# sch.net
KiCad netlist of a schematic drawn in Altium Designer
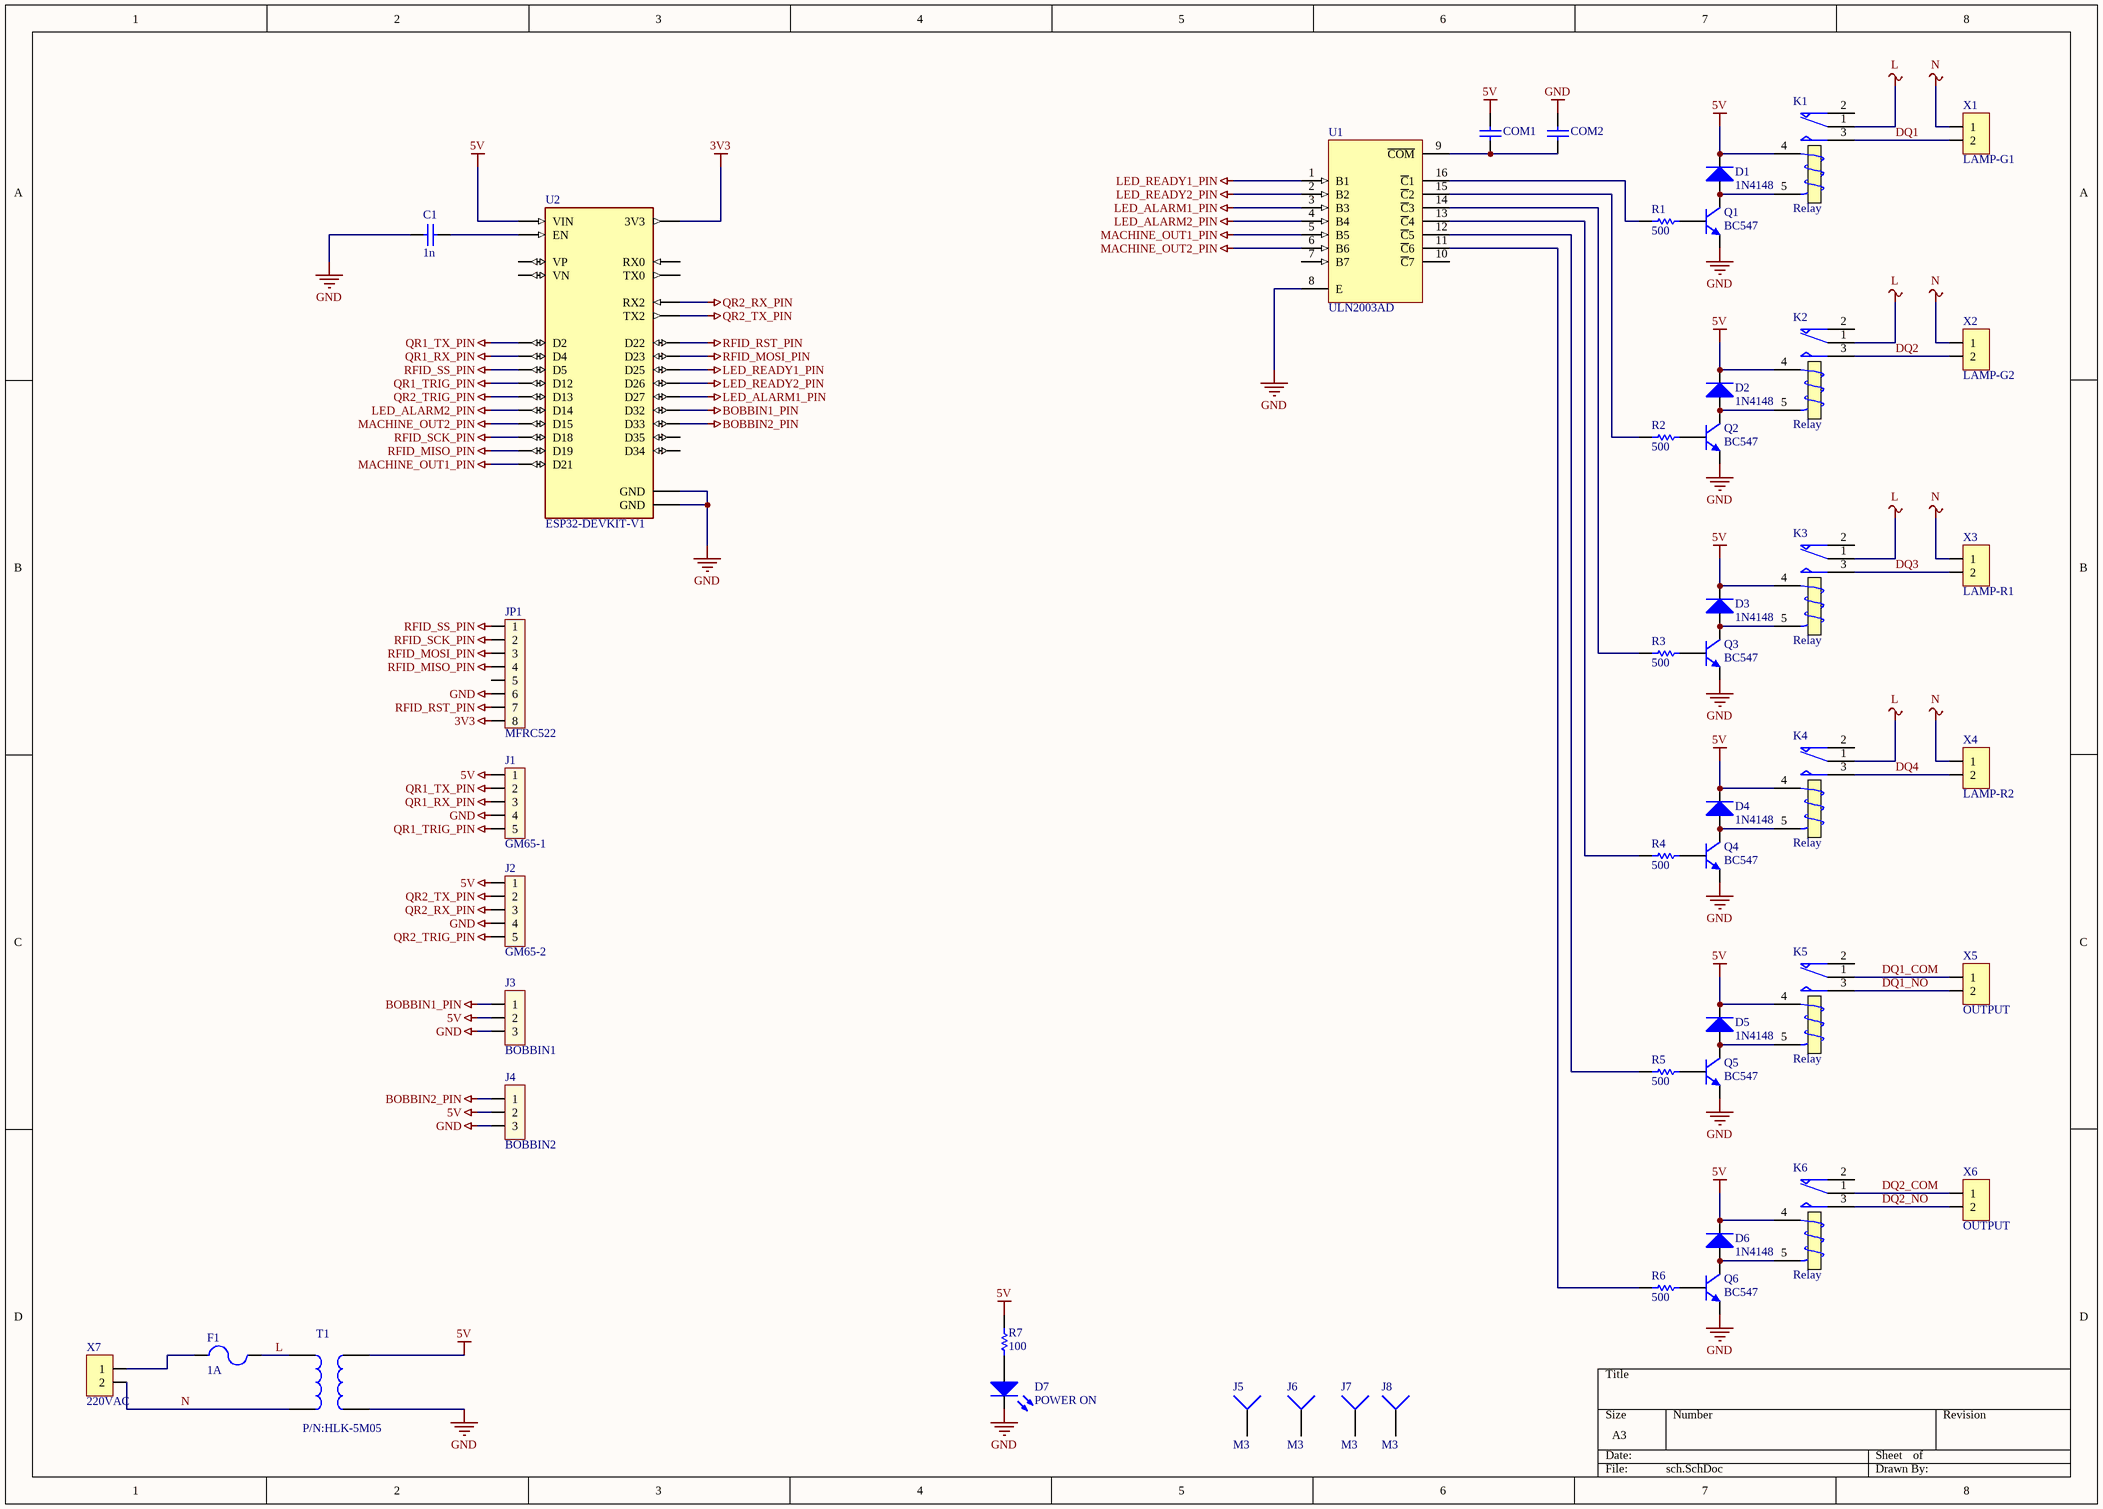
[diagram p0: sch.SchDoc]

(export (version "E")
  (design (tool "Eeschema 10.0.6"))
  (components
    (comp (ref "C1")
      (value "1n")
      (footprint "CR2012-0805")
      (description "Capacitor")
      (fields (field (name "PUBLISHER") "Altium Limited"))
      (libsource (lib "Miscellaneous Devices") (part "Cap"))
    )
    (comp (ref "COM1")
      (value "~")
      (footprint "CR2012-0805")
      (description "Capacitor")
      (fields (field (name "PUBLISHER") "Altium Limited"))
      (libsource (lib "Miscellaneous Devices") (part "Cap"))
    )
    (comp (ref "COM2")
      (value "~")
      (footprint "CR2012-0805")
      (description "Capacitor")
      (fields (field (name "PUBLISHER") "Altium Limited"))
      (libsource (lib "Miscellaneous Devices") (part "Cap"))
    )
    (comp (ref "D1")
      (value "1N4148")
      (footprint "D4148")
      (description "Default Diode")
      (fields (field (name "PUBLISHER") "Altium Limited"))
      (libsource (lib "weerachai") (part "Diode"))
    )
    (comp (ref "D2")
      (value "1N4148")
      (footprint "D4148")
      (description "Default Diode")
      (fields (field (name "PUBLISHER") "Altium Limited"))
      (libsource (lib "weerachai") (part "Diode"))
    )
    (comp (ref "D3")
      (value "1N4148")
      (footprint "D4148")
      (description "Default Diode")
      (fields (field (name "PUBLISHER") "Altium Limited"))
      (libsource (lib "weerachai") (part "Diode"))
    )
    (comp (ref "D4")
      (value "1N4148")
      (footprint "D4148")
      (description "Default Diode")
      (fields (field (name "PUBLISHER") "Altium Limited"))
      (libsource (lib "weerachai") (part "Diode"))
    )
    (comp (ref "D5")
      (value "1N4148")
      (footprint "D4148")
      (description "Default Diode")
      (fields (field (name "PUBLISHER") "Altium Limited"))
      (libsource (lib "weerachai") (part "Diode"))
    )
    (comp (ref "D6")
      (value "1N4148")
      (footprint "D4148")
      (description "Default Diode")
      (fields (field (name "PUBLISHER") "Altium Limited"))
      (libsource (lib "weerachai") (part "Diode"))
    )
    (comp (ref "D7")
      (value "POWER ON")
      (footprint "LED")
      (description "Typical INFRARED GaAs LED")
      (fields (field (name "PUBLISHER") "Altium Limited"))
      (libsource (lib "weerachai") (part "LED0"))
    )
    (comp (ref "F1")
      (value "1A")
      (footprint "CAP5W")
      (description "Fuse")
      (fields (field (name "PUBLISHER") "Altium Limited"))
      (libsource (lib "weerachai") (part "Fuse 2"))
    )
    (comp (ref "J1")
      (value "GM65-1")
      (footprint "CONNECT_2.54_(5)")
      (libsource (lib "My Library") (part "JP5"))
    )
    (comp (ref "J2")
      (value "GM65-2")
      (footprint "CONNECT_2.54_(5)")
      (libsource (lib "My Library") (part "JP5"))
    )
    (comp (ref "J3")
      (value "BOBBIN1")
      (footprint "CONNECT_W(3)")
      (description "Jumper 3")
      (libsource (lib "My Library") (part "JP3"))
    )
    (comp (ref "J4")
      (value "BOBBIN2")
      (footprint "CONNECT_W(3)")
      (description "Jumper 3")
      (libsource (lib "My Library") (part "JP3"))
    )
    (comp (ref "J5")
      (value "M3")
      (footprint "PAD")
      (description "Socket")
      (fields (field (name "PUBLISHER") "Altium Limited"))
      (libsource (lib "weerachai") (part "Socket"))
    )
    (comp (ref "J6")
      (value "M3")
      (footprint "PAD")
      (description "Socket")
      (fields (field (name "PUBLISHER") "Altium Limited"))
      (libsource (lib "weerachai") (part "Socket"))
    )
    (comp (ref "J7")
      (value "M3")
      (footprint "PAD")
      (description "Socket")
      (fields (field (name "PUBLISHER") "Altium Limited"))
      (libsource (lib "weerachai") (part "Socket"))
    )
    (comp (ref "J8")
      (value "M3")
      (footprint "PAD")
      (description "Socket")
      (fields (field (name "PUBLISHER") "Altium Limited"))
      (libsource (lib "weerachai") (part "Socket"))
    )
    (comp (ref "JP1")
      (value "MFRC522")
      (footprint "SIP8")
      (description "JP8 PIN")
      (libsource (lib "My Library") (part "JP8"))
    )
    (comp (ref "K1")
      (value "Relay")
      (footprint "RELAY1CON_REV")
      (description "SPDT Relay")
      (fields (field (name "PUBLISHER") "Altium Limited"))
      (libsource (lib "weerachai") (part "Relay"))
    )
    (comp (ref "K2")
      (value "Relay")
      (footprint "RELAY1CON_REV")
      (description "SPDT Relay")
      (fields (field (name "PUBLISHER") "Altium Limited"))
      (libsource (lib "weerachai") (part "Relay"))
    )
    (comp (ref "K3")
      (value "Relay")
      (footprint "RELAY1CON_REV")
      (description "SPDT Relay")
      (fields (field (name "PUBLISHER") "Altium Limited"))
      (libsource (lib "weerachai") (part "Relay"))
    )
    (comp (ref "K4")
      (value "Relay")
      (footprint "RELAY1CON_REV")
      (description "SPDT Relay")
      (fields (field (name "PUBLISHER") "Altium Limited"))
      (libsource (lib "weerachai") (part "Relay"))
    )
    (comp (ref "K5")
      (value "Relay")
      (footprint "RELAY1CON_REV")
      (description "SPDT Relay")
      (fields (field (name "PUBLISHER") "Altium Limited"))
      (libsource (lib "weerachai") (part "Relay"))
    )
    (comp (ref "K6")
      (value "Relay")
      (footprint "RELAY1CON_REV")
      (description "SPDT Relay")
      (fields (field (name "PUBLISHER") "Altium Limited"))
      (libsource (lib "weerachai") (part "Relay"))
    )
    (comp (ref "Q1")
      (value "BC547")
      (footprint "TO-92")
      (description "NPN General Purpose Amplifier")
      (fields (field (name "PUBLISHER") "Altium Limited"))
      (libsource (lib "weerachai") (part "2N3904"))
    )
    (comp (ref "Q2")
      (value "BC547")
      (footprint "TO-92")
      (description "NPN General Purpose Amplifier")
      (fields (field (name "PUBLISHER") "Altium Limited"))
      (libsource (lib "weerachai") (part "2N3904"))
    )
    (comp (ref "Q3")
      (value "BC547")
      (footprint "TO-92")
      (description "NPN General Purpose Amplifier")
      (fields (field (name "PUBLISHER") "Altium Limited"))
      (libsource (lib "weerachai") (part "2N3904"))
    )
    (comp (ref "Q4")
      (value "BC547")
      (footprint "TO-92")
      (description "NPN General Purpose Amplifier")
      (fields (field (name "PUBLISHER") "Altium Limited"))
      (libsource (lib "weerachai") (part "2N3904"))
    )
    (comp (ref "Q5")
      (value "BC547")
      (footprint "TO-92")
      (description "NPN General Purpose Amplifier")
      (fields (field (name "PUBLISHER") "Altium Limited"))
      (libsource (lib "weerachai") (part "2N3904"))
    )
    (comp (ref "Q6")
      (value "BC547")
      (footprint "TO-92")
      (description "NPN General Purpose Amplifier")
      (fields (field (name "PUBLISHER") "Altium Limited"))
      (libsource (lib "weerachai") (part "2N3904"))
    )
    (comp (ref "R1")
      (value "500")
      (footprint "R1/8")
      (description "Resistor")
      (fields (field (name "PUBLISHER") "Altium Limited"))
      (libsource (lib "weerachai") (part "Res1"))
    )
    (comp (ref "R2")
      (value "500")
      (footprint "R1/8")
      (description "Resistor")
      (fields (field (name "PUBLISHER") "Altium Limited"))
      (libsource (lib "weerachai") (part "Res1"))
    )
    (comp (ref "R3")
      (value "500")
      (footprint "R1/8")
      (description "Resistor")
      (fields (field (name "PUBLISHER") "Altium Limited"))
      (libsource (lib "weerachai") (part "Res1"))
    )
    (comp (ref "R4")
      (value "500")
      (footprint "R1/8")
      (description "Resistor")
      (fields (field (name "PUBLISHER") "Altium Limited"))
      (libsource (lib "weerachai") (part "Res1"))
    )
    (comp (ref "R5")
      (value "500")
      (footprint "R1/8")
      (description "Resistor")
      (fields (field (name "PUBLISHER") "Altium Limited"))
      (libsource (lib "weerachai") (part "Res1"))
    )
    (comp (ref "R6")
      (value "500")
      (footprint "R1/8")
      (description "Resistor")
      (fields (field (name "PUBLISHER") "Altium Limited"))
      (libsource (lib "weerachai") (part "Res1"))
    )
    (comp (ref "R7")
      (value "100")
      (footprint "R1/8")
      (description "Resistor")
      (fields (field (name "PUBLISHER") "Altium Limited"))
      (libsource (lib "weerachai") (part "Res1"))
    )
    (comp (ref "T1")
      (value "P/N:HLK-5M05")
      (footprint "HLK-PM01")
      (description "Transformer")
      (fields (field (name "PUBLISHER") "Altium Limited"))
      (libsource (lib "weerachai") (part "Trans"))
    )
    (comp (ref "U1")
      (value "ULN2003AD")
      (footprint "D016_N")
      (description "Darlington Transistor Array")
      (fields (field (name "PUBLISHER") "Altium Limited"))
      (libsource (lib "TI Interface Darlington Driver") (part "ULN2003AD"))
    )
    (comp (ref "U2")
      (value "ESP32-DEVKIT-V1")
      (footprint "ESP32-30PIN")
      (libsource (lib "weerachai") (part "ESP32-DEVKIT-V1"))
    )
    (comp (ref "X1")
      (value "LAMP-G1")
      (footprint "KF142V-5.08-P2")
      (description "WR-PHD 2.54 mm Angled Socket Header")
      (fields
        (field (name "MANUFACTURER") "Würth Elektronik eiSos GmbH")
        (field (name "PARTNO") "613002143121")
        (field (name "CREATED BY") "Karrer Zheng")
      )
      (libsource (lib "My Library") (part "JP2"))
    )
    (comp (ref "X2")
      (value "LAMP-G2")
      (footprint "KF142V-5.08-P2")
      (description "WR-PHD 2.54 mm Angled Socket Header")
      (fields
        (field (name "MANUFACTURER") "Würth Elektronik eiSos GmbH")
        (field (name "PARTNO") "613002143121")
        (field (name "CREATED BY") "Karrer Zheng")
      )
      (libsource (lib "My Library") (part "JP2"))
    )
    (comp (ref "X3")
      (value "LAMP-R1")
      (footprint "KF142V-5.08-P2")
      (description "WR-PHD 2.54 mm Angled Socket Header")
      (fields
        (field (name "MANUFACTURER") "Würth Elektronik eiSos GmbH")
        (field (name "PARTNO") "613002143121")
        (field (name "CREATED BY") "Karrer Zheng")
      )
      (libsource (lib "My Library") (part "JP2"))
    )
    (comp (ref "X4")
      (value "LAMP-R2")
      (footprint "KF142V-5.08-P2")
      (description "WR-PHD 2.54 mm Angled Socket Header")
      (fields
        (field (name "MANUFACTURER") "Würth Elektronik eiSos GmbH")
        (field (name "PARTNO") "613002143121")
        (field (name "CREATED BY") "Karrer Zheng")
      )
      (libsource (lib "My Library") (part "JP2"))
    )
    (comp (ref "X5")
      (value "OUTPUT")
      (footprint "KF142V-5.08-P2")
      (description "WR-PHD 2.54 mm Angled Socket Header")
      (fields
        (field (name "MANUFACTURER") "Würth Elektronik eiSos GmbH")
        (field (name "PARTNO") "613002143121")
        (field (name "CREATED BY") "Karrer Zheng")
      )
      (libsource (lib "My Library") (part "JP2"))
    )
    (comp (ref "X6")
      (value "OUTPUT")
      (footprint "KF142V-5.08-P2")
      (description "WR-PHD 2.54 mm Angled Socket Header")
      (fields
        (field (name "MANUFACTURER") "Würth Elektronik eiSos GmbH")
        (field (name "PARTNO") "613002143121")
        (field (name "CREATED BY") "Karrer Zheng")
      )
      (libsource (lib "My Library") (part "JP2"))
    )
    (comp (ref "X7")
      (value "220VAC")
      (footprint "KF142V-5.08-P2")
      (description "WR-PHD 2.54 mm Angled Socket Header")
      (fields
        (field (name "MANUFACTURER") "Würth Elektronik eiSos GmbH")
        (field (name "PARTNO") "613002143121")
        (field (name "CREATED BY") "Karrer Zheng")
      )
      (libsource (lib "") (part "JP2_1"))
    )
  )
  (nets
    (net (code "1") (name "/DQ1") (class "Default")
      (node (ref "K1") (pin "3") (pinfunction "NO_3") (pintype "passive"))
      (node (ref "X1") (pin "2") (pinfunction "2_2") (pintype "passive"))
    )
    (net (code "2") (name "/DQ1_COM") (class "Default")
      (node (ref "K5") (pin "1") (pinfunction "COM_1") (pintype "passive"))
      (node (ref "X5") (pin "1") (pinfunction "1_1") (pintype "passive"))
    )
    (net (code "3") (name "/DQ1_NO") (class "Default")
      (node (ref "K5") (pin "3") (pinfunction "NO_3") (pintype "passive"))
      (node (ref "X5") (pin "2") (pinfunction "2_2") (pintype "passive"))
    )
    (net (code "4") (name "/DQ2") (class "Default")
      (node (ref "K2") (pin "3") (pinfunction "NO_3") (pintype "passive"))
      (node (ref "X2") (pin "2") (pinfunction "2_2") (pintype "passive"))
    )
    (net (code "5") (name "/DQ2_COM") (class "Default")
      (node (ref "K6") (pin "1") (pinfunction "COM_1") (pintype "passive"))
      (node (ref "X6") (pin "1") (pinfunction "1_1") (pintype "passive"))
    )
    (net (code "6") (name "/DQ2_NO") (class "Default")
      (node (ref "K6") (pin "3") (pinfunction "NO_3") (pintype "passive"))
      (node (ref "X6") (pin "2") (pinfunction "2_2") (pintype "passive"))
    )
    (net (code "7") (name "/DQ3") (class "Default")
      (node (ref "K3") (pin "3") (pinfunction "NO_3") (pintype "passive"))
      (node (ref "X3") (pin "2") (pinfunction "2_2") (pintype "passive"))
    )
    (net (code "8") (name "/DQ4") (class "Default")
      (node (ref "K4") (pin "3") (pinfunction "NO_3") (pintype "passive"))
      (node (ref "X4") (pin "2") (pinfunction "2_2") (pintype "passive"))
    )
    (net (code "9") (name "3V3") (class "Default")
      (node (ref "JP1") (pin "8") (pinfunction "8_8") (pintype "passive"))
      (node (ref "U2") (pin "1") (pinfunction "3V3_1") (pintype "output"))
    )
    (net (code "10") (name "5V") (class "Default")
      (node (ref "COM1") (pin "2") (pinfunction "2_2") (pintype "passive"))
      (node (ref "D1") (pin "K") (pinfunction "K_K") (pintype "passive"))
      (node (ref "D2") (pin "K") (pinfunction "K_K") (pintype "passive"))
      (node (ref "D3") (pin "K") (pinfunction "K_K") (pintype "passive"))
      (node (ref "D4") (pin "K") (pinfunction "K_K") (pintype "passive"))
      (node (ref "D5") (pin "K") (pinfunction "K_K") (pintype "passive"))
      (node (ref "D6") (pin "K") (pinfunction "K_K") (pintype "passive"))
      (node (ref "J1") (pin "1") (pinfunction "1_1") (pintype "passive"))
      (node (ref "J2") (pin "1") (pinfunction "1_1") (pintype "passive"))
      (node (ref "J3") (pin "2") (pinfunction "2_2") (pintype "passive"))
      (node (ref "J4") (pin "2") (pinfunction "2_2") (pintype "passive"))
      (node (ref "K1") (pin "4") (pinfunction "T1_4") (pintype "passive"))
      (node (ref "K2") (pin "4") (pinfunction "T1_4") (pintype "passive"))
      (node (ref "K3") (pin "4") (pinfunction "T1_4") (pintype "passive"))
      (node (ref "K4") (pin "4") (pinfunction "T1_4") (pintype "passive"))
      (node (ref "K5") (pin "4") (pinfunction "T1_4") (pintype "passive"))
      (node (ref "K6") (pin "4") (pinfunction "T1_4") (pintype "passive"))
      (node (ref "R7") (pin "1") (pinfunction "1_1") (pintype "passive"))
      (node (ref "T1") (pin "4") (pinfunction "4_4") (pintype "passive"))
      (node (ref "U2") (pin "30") (pinfunction "VIN_30") (pintype "input"))
    )
    (net (code "11") (name "BOBBIN1_PIN") (class "Default")
      (node (ref "J3") (pin "1") (pinfunction "1_1") (pintype "passive"))
      (node (ref "U2") (pin "21") (pinfunction "D32_21") (pintype "bidirectional"))
    )
    (net (code "12") (name "BOBBIN2_PIN") (class "Default")
      (node (ref "J4") (pin "1") (pinfunction "1_1") (pintype "passive"))
      (node (ref "U2") (pin "22") (pinfunction "D33_22") (pintype "bidirectional"))
    )
    (net (code "13") (name "GND") (class "Default")
      (node (ref "C1") (pin "1") (pinfunction "1_1") (pintype "passive"))
      (node (ref "COM2") (pin "2") (pinfunction "2_2") (pintype "passive"))
      (node (ref "D7") (pin "2") (pinfunction "K_2") (pintype "passive"))
      (node (ref "J1") (pin "4") (pinfunction "4_4") (pintype "passive"))
      (node (ref "J2") (pin "4") (pinfunction "4_4") (pintype "passive"))
      (node (ref "J3") (pin "3") (pinfunction "3_3") (pintype "passive"))
      (node (ref "J4") (pin "3") (pinfunction "3_3") (pintype "passive"))
      (node (ref "JP1") (pin "6") (pinfunction "6_6") (pintype "passive"))
      (node (ref "Q1") (pin "3") (pinfunction "E_3") (pintype "passive"))
      (node (ref "Q2") (pin "3") (pinfunction "E_3") (pintype "passive"))
      (node (ref "Q3") (pin "3") (pinfunction "E_3") (pintype "passive"))
      (node (ref "Q4") (pin "3") (pinfunction "E_3") (pintype "passive"))
      (node (ref "Q5") (pin "3") (pinfunction "E_3") (pintype "passive"))
      (node (ref "Q6") (pin "3") (pinfunction "E_3") (pintype "passive"))
      (node (ref "T1") (pin "3") (pinfunction "3_3") (pintype "passive"))
      (node (ref "U1") (pin "8") (pinfunction "E_8") (pintype "power_in"))
      (node (ref "U2") (pin "2") (pinfunction "GND_2") (pintype "power_in"))
      (node (ref "U2") (pin "29") (pinfunction "GND_29") (pintype "power_in"))
    )
    (net (code "14") (name "L") (class "Default")
      (node (ref "F1") (pin "2") (pinfunction "2_2") (pintype "passive"))
      (node (ref "K1") (pin "1") (pinfunction "COM_1") (pintype "passive"))
      (node (ref "K2") (pin "1") (pinfunction "COM_1") (pintype "passive"))
      (node (ref "K3") (pin "1") (pinfunction "COM_1") (pintype "passive"))
      (node (ref "K4") (pin "1") (pinfunction "COM_1") (pintype "passive"))
      (node (ref "T1") (pin "2") (pinfunction "2_2") (pintype "passive"))
    )
    (net (code "15") (name "LED_ALARM1_PIN") (class "Default")
      (node (ref "U1") (pin "3") (pinfunction "B3_3") (pintype "input"))
      (node (ref "U2") (pin "25") (pinfunction "D27_25") (pintype "bidirectional"))
    )
    (net (code "16") (name "LED_ALARM2_PIN") (class "Default")
      (node (ref "U1") (pin "4") (pinfunction "B4_4") (pintype "input"))
      (node (ref "U2") (pin "26") (pinfunction "D14_26") (pintype "bidirectional"))
    )
    (net (code "17") (name "LED_READY1_PIN") (class "Default")
      (node (ref "U1") (pin "1") (pinfunction "B1_1") (pintype "input"))
      (node (ref "U2") (pin "23") (pinfunction "D25_23") (pintype "bidirectional"))
    )
    (net (code "18") (name "LED_READY2_PIN") (class "Default")
      (node (ref "U1") (pin "2") (pinfunction "B2_2") (pintype "input"))
      (node (ref "U2") (pin "24") (pinfunction "D26_24") (pintype "bidirectional"))
    )
    (net (code "19") (name "MACHINE_OUT1_PIN") (class "Default")
      (node (ref "U1") (pin "5") (pinfunction "B5_5") (pintype "input"))
      (node (ref "U2") (pin "11") (pinfunction "D21_11") (pintype "bidirectional"))
    )
    (net (code "20") (name "MACHINE_OUT2_PIN") (class "Default")
      (node (ref "U1") (pin "6") (pinfunction "B6_6") (pintype "input"))
      (node (ref "U2") (pin "3") (pinfunction "D15_3") (pintype "bidirectional"))
    )
    (net (code "21") (name "N") (class "Default")
      (node (ref "T1") (pin "1") (pinfunction "1_1") (pintype "passive"))
      (node (ref "X1") (pin "1") (pinfunction "1_1") (pintype "passive"))
      (node (ref "X2") (pin "1") (pinfunction "1_1") (pintype "passive"))
      (node (ref "X3") (pin "1") (pinfunction "1_1") (pintype "passive"))
      (node (ref "X4") (pin "1") (pinfunction "1_1") (pintype "passive"))
      (node (ref "X7") (pin "2") (pinfunction "2_2") (pintype "passive"))
    )
    (net (code "22") (name "Net-(D7-A)") (class "Default")
      (node (ref "D7") (pin "1") (pinfunction "A_1") (pintype "passive"))
      (node (ref "R7") (pin "2") (pinfunction "2_2") (pintype "passive"))
    )
    (net (code "23") (name "Net-(F1-Pad1)") (class "Default")
      (node (ref "F1") (pin "1") (pinfunction "1_1") (pintype "passive"))
      (node (ref "X7") (pin "1") (pinfunction "1_1") (pintype "passive"))
    )
    (net (code "24") (name "Net-(K1-T2)") (class "Default")
      (node (ref "D1") (pin "A") (pinfunction "A_A") (pintype "passive"))
      (node (ref "K1") (pin "5") (pinfunction "T2_5") (pintype "passive"))
      (node (ref "Q1") (pin "1") (pinfunction "C_1") (pintype "passive"))
    )
    (net (code "25") (name "Net-(K2-T2)") (class "Default")
      (node (ref "D2") (pin "A") (pinfunction "A_A") (pintype "passive"))
      (node (ref "K2") (pin "5") (pinfunction "T2_5") (pintype "passive"))
      (node (ref "Q2") (pin "1") (pinfunction "C_1") (pintype "passive"))
    )
    (net (code "26") (name "Net-(K3-T2)") (class "Default")
      (node (ref "D3") (pin "A") (pinfunction "A_A") (pintype "passive"))
      (node (ref "K3") (pin "5") (pinfunction "T2_5") (pintype "passive"))
      (node (ref "Q3") (pin "1") (pinfunction "C_1") (pintype "passive"))
    )
    (net (code "27") (name "Net-(K4-T2)") (class "Default")
      (node (ref "D4") (pin "A") (pinfunction "A_A") (pintype "passive"))
      (node (ref "K4") (pin "5") (pinfunction "T2_5") (pintype "passive"))
      (node (ref "Q4") (pin "1") (pinfunction "C_1") (pintype "passive"))
    )
    (net (code "28") (name "Net-(K5-T2)") (class "Default")
      (node (ref "D5") (pin "A") (pinfunction "A_A") (pintype "passive"))
      (node (ref "K5") (pin "5") (pinfunction "T2_5") (pintype "passive"))
      (node (ref "Q5") (pin "1") (pinfunction "C_1") (pintype "passive"))
    )
    (net (code "29") (name "Net-(K6-T2)") (class "Default")
      (node (ref "D6") (pin "A") (pinfunction "A_A") (pintype "passive"))
      (node (ref "K6") (pin "5") (pinfunction "T2_5") (pintype "passive"))
      (node (ref "Q6") (pin "1") (pinfunction "C_1") (pintype "passive"))
    )
    (net (code "30") (name "Net-(Q1-B)") (class "Default")
      (node (ref "Q1") (pin "2") (pinfunction "B_2") (pintype "passive"))
      (node (ref "R1") (pin "1") (pinfunction "1_1") (pintype "passive"))
    )
    (net (code "31") (name "Net-(Q2-B)") (class "Default")
      (node (ref "Q2") (pin "2") (pinfunction "B_2") (pintype "passive"))
      (node (ref "R2") (pin "1") (pinfunction "1_1") (pintype "passive"))
    )
    (net (code "32") (name "Net-(Q3-B)") (class "Default")
      (node (ref "Q3") (pin "2") (pinfunction "B_2") (pintype "passive"))
      (node (ref "R3") (pin "1") (pinfunction "1_1") (pintype "passive"))
    )
    (net (code "33") (name "Net-(Q4-B)") (class "Default")
      (node (ref "Q4") (pin "2") (pinfunction "B_2") (pintype "passive"))
      (node (ref "R4") (pin "1") (pinfunction "1_1") (pintype "passive"))
    )
    (net (code "34") (name "Net-(Q5-B)") (class "Default")
      (node (ref "Q5") (pin "2") (pinfunction "B_2") (pintype "passive"))
      (node (ref "R5") (pin "1") (pinfunction "1_1") (pintype "passive"))
    )
    (net (code "35") (name "Net-(Q6-B)") (class "Default")
      (node (ref "Q6") (pin "2") (pinfunction "B_2") (pintype "passive"))
      (node (ref "R6") (pin "1") (pinfunction "1_1") (pintype "passive"))
    )
    (net (code "36") (name "Net-(U1-~{COM})") (class "Default")
      (node (ref "COM1") (pin "1") (pinfunction "1_1") (pintype "passive"))
      (node (ref "COM2") (pin "1") (pinfunction "1_1") (pintype "passive"))
      (node (ref "U1") (pin "9") (pinfunction "~{COM}_9") (pintype "passive"))
    )
    (net (code "37") (name "Net-(U1-~{C}1)") (class "Default")
      (node (ref "R1") (pin "2") (pinfunction "2_2") (pintype "passive"))
      (node (ref "U1") (pin "16") (pinfunction "~{C}1_16") (pintype "open_collector"))
    )
    (net (code "38") (name "Net-(U1-~{C}2)") (class "Default")
      (node (ref "R2") (pin "2") (pinfunction "2_2") (pintype "passive"))
      (node (ref "U1") (pin "15") (pinfunction "~{C}2_15") (pintype "open_collector"))
    )
    (net (code "39") (name "Net-(U1-~{C}3)") (class "Default")
      (node (ref "R3") (pin "2") (pinfunction "2_2") (pintype "passive"))
      (node (ref "U1") (pin "14") (pinfunction "~{C}3_14") (pintype "open_collector"))
    )
    (net (code "40") (name "Net-(U1-~{C}4)") (class "Default")
      (node (ref "R4") (pin "2") (pinfunction "2_2") (pintype "passive"))
      (node (ref "U1") (pin "13") (pinfunction "~{C}4_13") (pintype "open_collector"))
    )
    (net (code "41") (name "Net-(U1-~{C}5)") (class "Default")
      (node (ref "R5") (pin "2") (pinfunction "2_2") (pintype "passive"))
      (node (ref "U1") (pin "12") (pinfunction "~{C}5_12") (pintype "open_collector"))
    )
    (net (code "42") (name "Net-(U1-~{C}6)") (class "Default")
      (node (ref "R6") (pin "2") (pinfunction "2_2") (pintype "passive"))
      (node (ref "U1") (pin "11") (pinfunction "~{C}6_11") (pintype "open_collector"))
    )
    (net (code "43") (name "Net-(U2-EN)") (class "Default")
      (node (ref "C1") (pin "2") (pinfunction "2_2") (pintype "passive"))
      (node (ref "U2") (pin "16") (pinfunction "EN_16") (pintype "input"))
    )
    (net (code "44") (name "QR1_RX_PIN") (class "Default")
      (node (ref "J1") (pin "3") (pinfunction "3_3") (pintype "passive"))
      (node (ref "U2") (pin "5") (pinfunction "D4_5") (pintype "bidirectional"))
    )
    (net (code "45") (name "QR1_TRIG_PIN") (class "Default")
      (node (ref "J1") (pin "5") (pinfunction "5_5") (pintype "passive"))
      (node (ref "U2") (pin "27") (pinfunction "D12_27") (pintype "bidirectional"))
    )
    (net (code "46") (name "QR1_TX_PIN") (class "Default")
      (node (ref "J1") (pin "2") (pinfunction "2_2") (pintype "passive"))
      (node (ref "U2") (pin "4") (pinfunction "D2_4") (pintype "bidirectional"))
    )
    (net (code "47") (name "QR2_RX_PIN") (class "Default")
      (node (ref "J2") (pin "3") (pinfunction "3_3") (pintype "passive"))
      (node (ref "U2") (pin "6") (pinfunction "RX2_6") (pintype "input"))
    )
    (net (code "48") (name "QR2_TRIG_PIN") (class "Default")
      (node (ref "J2") (pin "5") (pinfunction "5_5") (pintype "passive"))
      (node (ref "U2") (pin "28") (pinfunction "D13_28") (pintype "bidirectional"))
    )
    (net (code "49") (name "QR2_TX_PIN") (class "Default")
      (node (ref "J2") (pin "2") (pinfunction "2_2") (pintype "passive"))
      (node (ref "U2") (pin "7") (pinfunction "TX2_7") (pintype "output"))
    )
    (net (code "50") (name "RFID_MISO_PIN") (class "Default")
      (node (ref "JP1") (pin "4") (pinfunction "4_4") (pintype "passive"))
      (node (ref "U2") (pin "10") (pinfunction "D19_10") (pintype "bidirectional"))
    )
    (net (code "51") (name "RFID_MOSI_PIN") (class "Default")
      (node (ref "JP1") (pin "3") (pinfunction "3_3") (pintype "passive"))
      (node (ref "U2") (pin "15") (pinfunction "D23_15") (pintype "bidirectional"))
    )
    (net (code "52") (name "RFID_RST_PIN") (class "Default")
      (node (ref "JP1") (pin "7") (pinfunction "7_7") (pintype "passive"))
      (node (ref "U2") (pin "14") (pinfunction "D22_14") (pintype "bidirectional"))
    )
    (net (code "53") (name "RFID_SCK_PIN") (class "Default")
      (node (ref "JP1") (pin "2") (pinfunction "2_2") (pintype "passive"))
      (node (ref "U2") (pin "9") (pinfunction "D18_9") (pintype "bidirectional"))
    )
    (net (code "54") (name "RFID_SS_PIN") (class "Default")
      (node (ref "JP1") (pin "1") (pinfunction "1_1") (pintype "passive"))
      (node (ref "U2") (pin "8") (pinfunction "D5_8") (pintype "bidirectional"))
    )
    (net (code "55") (name "unconnected-(J5-Pad1)") (class "Default")
      (node (ref "J5") (pin "1") (pinfunction "1_1") (pintype "passive"))
    )
    (net (code "56") (name "unconnected-(J6-Pad1)") (class "Default")
      (node (ref "J6") (pin "1") (pinfunction "1_1") (pintype "passive"))
    )
    (net (code "57") (name "unconnected-(J7-Pad1)") (class "Default")
      (node (ref "J7") (pin "1") (pinfunction "1_1") (pintype "passive"))
    )
    (net (code "58") (name "unconnected-(J8-Pad1)") (class "Default")
      (node (ref "J8") (pin "1") (pinfunction "1_1") (pintype "passive"))
    )
    (net (code "59") (name "unconnected-(JP1-Pad5)") (class "Default")
      (node (ref "JP1") (pin "5") (pinfunction "5_5") (pintype "passive"))
    )
    (net (code "60") (name "unconnected-(K1-NC-Pad2)") (class "Default")
      (node (ref "K1") (pin "2") (pinfunction "NC_2") (pintype "passive"))
    )
    (net (code "61") (name "unconnected-(K2-NC-Pad2)") (class "Default")
      (node (ref "K2") (pin "2") (pinfunction "NC_2") (pintype "passive"))
    )
    (net (code "62") (name "unconnected-(K3-NC-Pad2)") (class "Default")
      (node (ref "K3") (pin "2") (pinfunction "NC_2") (pintype "passive"))
    )
    (net (code "63") (name "unconnected-(K4-NC-Pad2)") (class "Default")
      (node (ref "K4") (pin "2") (pinfunction "NC_2") (pintype "passive"))
    )
    (net (code "64") (name "unconnected-(K5-NC-Pad2)") (class "Default")
      (node (ref "K5") (pin "2") (pinfunction "NC_2") (pintype "passive"))
    )
    (net (code "65") (name "unconnected-(K6-NC-Pad2)") (class "Default")
      (node (ref "K6") (pin "2") (pinfunction "NC_2") (pintype "passive"))
    )
    (net (code "66") (name "unconnected-(U1-B7-Pad7)") (class "Default")
      (node (ref "U1") (pin "7") (pinfunction "B7_7") (pintype "input"))
    )
    (net (code "67") (name "unconnected-(U1-~{C}7-Pad10)") (class "Default")
      (node (ref "U1") (pin "10") (pinfunction "~{C}7_10") (pintype "open_collector"))
    )
    (net (code "68") (name "unconnected-(U2-D34-Pad19)") (class "Default")
      (node (ref "U2") (pin "19") (pinfunction "D34_19") (pintype "bidirectional"))
    )
    (net (code "69") (name "unconnected-(U2-D35-Pad20)") (class "Default")
      (node (ref "U2") (pin "20") (pinfunction "D35_20") (pintype "bidirectional"))
    )
    (net (code "70") (name "unconnected-(U2-RX0-Pad12)") (class "Default")
      (node (ref "U2") (pin "12") (pinfunction "RX0_12") (pintype "input"))
    )
    (net (code "71") (name "unconnected-(U2-TX0-Pad13)") (class "Default")
      (node (ref "U2") (pin "13") (pinfunction "TX0_13") (pintype "output"))
    )
    (net (code "72") (name "unconnected-(U2-VN-Pad18)") (class "Default")
      (node (ref "U2") (pin "18") (pinfunction "VN_18") (pintype "bidirectional"))
    )
    (net (code "73") (name "unconnected-(U2-VP-Pad17)") (class "Default")
      (node (ref "U2") (pin "17") (pinfunction "VP_17") (pintype "bidirectional"))
    )
  )
)
